# AMU_POC_final.net
KiCad netlist of a schematic drawn in Altium Designer
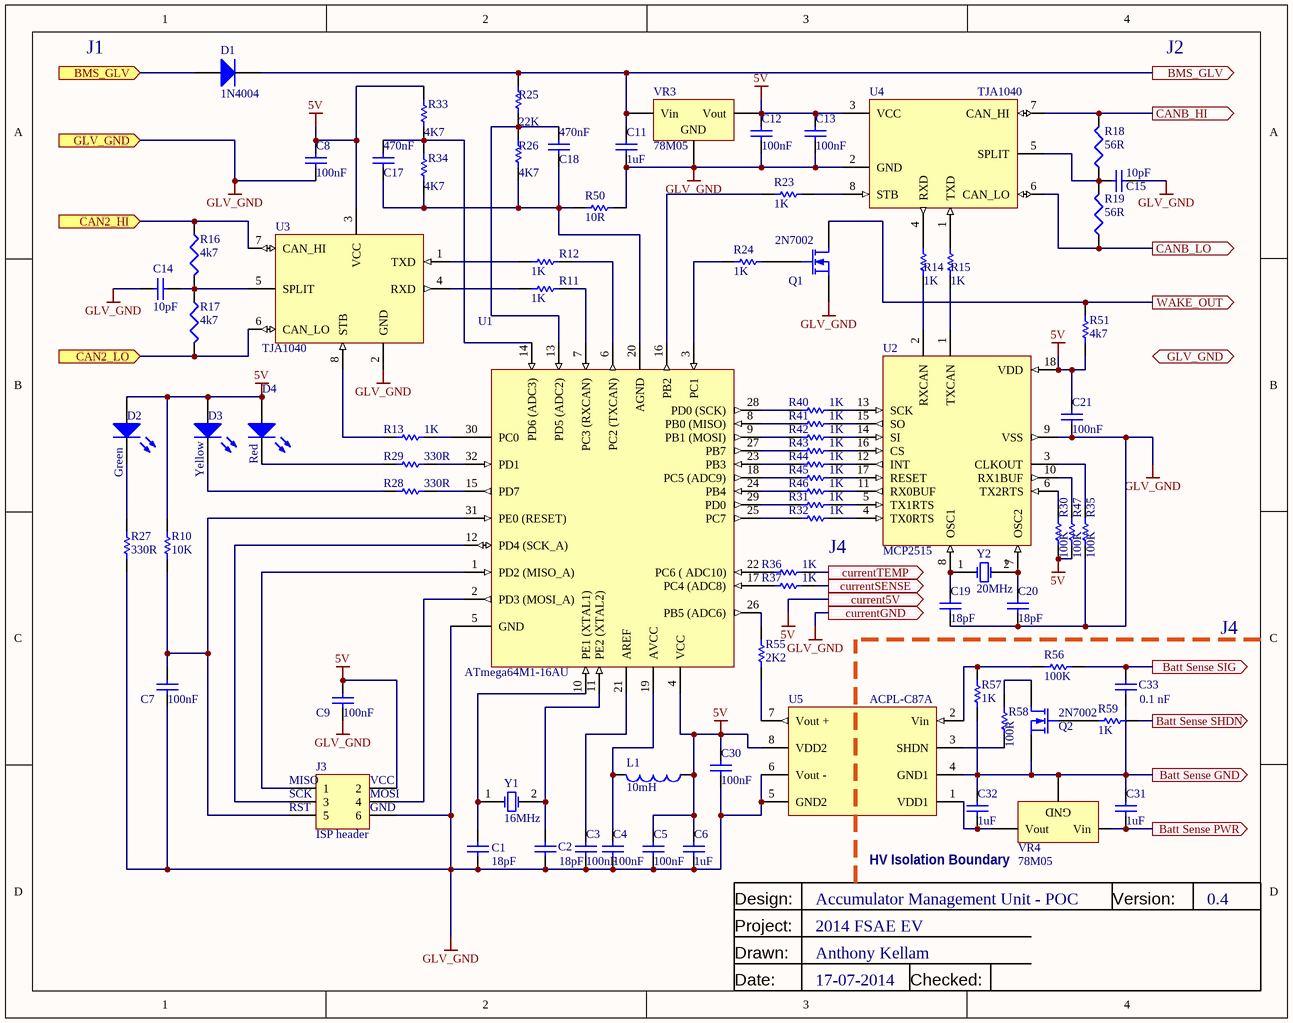
[diagram p0: AMU_POC_final.SchDoc]

(export (version "E")
  (design (tool "Eeschema 10.0.6"))
  (components
    (comp (ref "C1")
      (value "18pF")
      (footprint "0402")
      (description "Capacitor (Semiconductor SIM Model)")
      (fields (field (name "Comment") "Cap Semi") (field (name "PUBLISHER") "Altium Limited"))
      (libsource (lib "Miscellaneous Devices") (part "Cap Semi"))
    )
    (comp (ref "C2")
      (value "18pF")
      (footprint "0402")
      (description "Capacitor (Semiconductor SIM Model)")
      (fields (field (name "Comment") "Cap Semi") (field (name "PUBLISHER") "Altium Limited"))
      (libsource (lib "Miscellaneous Devices") (part "Cap Semi"))
    )
    (comp (ref "C3")
      (value "100nF")
      (footprint "0402")
      (description "Capacitor (Semiconductor SIM Model)")
      (fields (field (name "Comment") "Cap Semi") (field (name "PUBLISHER") "Altium Limited"))
      (libsource (lib "Miscellaneous Devices") (part "Cap Semi"))
    )
    (comp (ref "C4")
      (value "100nF")
      (footprint "0402")
      (description "Capacitor (Semiconductor SIM Model)")
      (fields (field (name "Comment") "Cap Semi") (field (name "PUBLISHER") "Altium Limited"))
      (libsource (lib "Miscellaneous Devices") (part "Cap Semi"))
    )
    (comp (ref "C5")
      (value "100nF")
      (footprint "0402")
      (description "Capacitor (Semiconductor SIM Model)")
      (fields (field (name "Comment") "Cap Semi") (field (name "PUBLISHER") "Altium Limited"))
      (libsource (lib "Miscellaneous Devices") (part "Cap Semi"))
    )
    (comp (ref "C6")
      (value "1uF")
      (footprint "0402")
      (description "Capacitor (Semiconductor SIM Model)")
      (fields (field (name "Comment") "Cap Semi") (field (name "PUBLISHER") "Altium Limited"))
      (libsource (lib "Miscellaneous Devices") (part "Cap Semi"))
    )
    (comp (ref "C7")
      (value "100nF")
      (footprint "0402")
      (description "Capacitor (Semiconductor SIM Model)")
      (fields (field (name "Comment") "Cap Semi") (field (name "PUBLISHER") "Altium Limited"))
      (libsource (lib "Miscellaneous Devices") (part "Cap Semi"))
    )
    (comp (ref "C8")
      (value "100nF")
      (footprint "0402")
      (description "Capacitor (Semiconductor SIM Model)")
      (fields (field (name "Comment") "Cap Semi") (field (name "PUBLISHER") "Altium Limited"))
      (libsource (lib "Miscellaneous Devices") (part "Cap Semi"))
    )
    (comp (ref "C9")
      (value "100nF")
      (footprint "0402")
      (description "Capacitor (Semiconductor SIM Model)")
      (fields (field (name "Comment") "Cap Semi") (field (name "PUBLISHER") "Altium Limited"))
      (libsource (lib "Miscellaneous Devices") (part "Cap Semi"))
    )
    (comp (ref "C11")
      (value "1uF")
      (footprint "0402")
      (description "Capacitor (Semiconductor SIM Model)")
      (fields (field (name "Comment") "Cap Semi") (field (name "PUBLISHER") "Altium Limited"))
      (libsource (lib "Miscellaneous Devices") (part "Cap Semi"))
    )
    (comp (ref "C12")
      (value "100nF")
      (footprint "0402")
      (description "Capacitor (Semiconductor SIM Model)")
      (fields (field (name "Comment") "Cap Semi") (field (name "PUBLISHER") "Altium Limited"))
      (libsource (lib "Miscellaneous Devices") (part "Cap Semi"))
    )
    (comp (ref "C13")
      (value "100nF")
      (footprint "0402")
      (description "Capacitor (Semiconductor SIM Model)")
      (fields (field (name "Comment") "Cap Semi") (field (name "PUBLISHER") "Altium Limited"))
      (libsource (lib "Miscellaneous Devices") (part "Cap Semi"))
    )
    (comp (ref "C14")
      (value "10pF")
      (footprint "0402")
      (description "Capacitor (Semiconductor SIM Model)")
      (fields (field (name "Comment") "Cap Semi") (field (name "PUBLISHER") "Altium Limited"))
      (libsource (lib "Miscellaneous Devices") (part "Cap Semi"))
    )
    (comp (ref "C15")
      (value "10pF")
      (footprint "0402")
      (description "Capacitor (Semiconductor SIM Model)")
      (fields (field (name "Comment") "Cap Semi") (field (name "PUBLISHER") "Altium Limited"))
      (libsource (lib "Miscellaneous Devices") (part "Cap Semi"))
    )
    (comp (ref "C17")
      (value "470nF")
      (footprint "0402")
      (description "Capacitor (Semiconductor SIM Model)")
      (fields (field (name "Comment") "Cap Semi") (field (name "PUBLISHER") "Altium Limited"))
      (libsource (lib "Miscellaneous Devices") (part "Cap Semi"))
    )
    (comp (ref "C18")
      (value "470nF")
      (footprint "0402")
      (description "Capacitor (Semiconductor SIM Model)")
      (fields (field (name "Comment") "Cap Semi") (field (name "PUBLISHER") "Altium Limited"))
      (libsource (lib "Miscellaneous Devices") (part "Cap Semi"))
    )
    (comp (ref "C19")
      (value "18pF")
      (footprint "0402")
      (description "Capacitor (Semiconductor SIM Model)")
      (fields (field (name "Comment") "Cap Semi") (field (name "PUBLISHER") "Altium Limited"))
      (libsource (lib "Miscellaneous Devices") (part "Cap Semi"))
    )
    (comp (ref "C20")
      (value "18pF")
      (footprint "0402")
      (description "Capacitor (Semiconductor SIM Model)")
      (fields (field (name "Comment") "Cap Semi") (field (name "PUBLISHER") "Altium Limited"))
      (libsource (lib "Miscellaneous Devices") (part "Cap Semi"))
    )
    (comp (ref "C21")
      (value "100nF")
      (footprint "0402")
      (description "Capacitor (Semiconductor SIM Model)")
      (fields (field (name "Comment") "Cap Semi") (field (name "PUBLISHER") "Altium Limited"))
      (libsource (lib "Miscellaneous Devices") (part "Cap Semi"))
    )
    (comp (ref "C30")
      (value "100nF")
      (footprint "0402")
      (description "Capacitor (Semiconductor SIM Model)")
      (fields (field (name "Comment") "Cap Semi") (field (name "PUBLISHER") "Altium Limited"))
      (libsource (lib "Miscellaneous Devices") (part "Cap Semi"))
    )
    (comp (ref "C31")
      (value "1uF")
      (footprint "0402")
      (description "Capacitor (Semiconductor SIM Model)")
      (fields (field (name "Comment") "Cap Semi") (field (name "PUBLISHER") "Altium Limited"))
      (libsource (lib "Miscellaneous Devices") (part "Cap Semi"))
    )
    (comp (ref "C32")
      (value "1uF")
      (footprint "0402")
      (description "Capacitor (Semiconductor SIM Model)")
      (fields (field (name "Comment") "Cap Semi") (field (name "PUBLISHER") "Altium Limited"))
      (libsource (lib "Miscellaneous Devices") (part "Cap Semi"))
    )
    (comp (ref "C33")
      (value "0.1 nF")
      (footprint "0402")
      (description "Capacitor (Semiconductor SIM Model)")
      (fields (field (name "Comment") "Cap Semi") (field (name "PUBLISHER") "Altium Limited"))
      (libsource (lib "Miscellaneous Devices") (part "Cap Semi"))
    )
    (comp (ref "D1")
      (value "1N4004")
      (footprint "SMC")
      (description "Default Diode")
      (fields (field (name "PUBLISHER") "Altium Limited"))
      (libsource (lib "Miscellaneous Devices") (part "Diode"))
    )
    (comp (ref "D2")
      (value "Green")
      (footprint "3.2X1.6X1.1")
      (description "Typical RED, GREEN, YELLOW, AMBER GaAs LED")
      (fields (field (name "PUBLISHER") "Altium Limited"))
      (libsource (lib "Miscellaneous Devices") (part "LED2"))
    )
    (comp (ref "D3")
      (value "Yellow")
      (footprint "3.2X1.6X1.1")
      (description "Typical RED, GREEN, YELLOW, AMBER GaAs LED")
      (fields (field (name "PUBLISHER") "Altium Limited"))
      (libsource (lib "Miscellaneous Devices") (part "LED2"))
    )
    (comp (ref "D4")
      (value "Red")
      (footprint "3.2X1.6X1.1")
      (description "Typical RED, GREEN, YELLOW, AMBER GaAs LED")
      (fields (field (name "PUBLISHER") "Altium Limited"))
      (libsource (lib "Miscellaneous Devices") (part "LED2"))
    )
    (comp (ref "J3")
      (value "ISP header")
      (footprint "HDR2X3")
      (description "Header, 3-Pin, Dual row")
      (fields (field (name "PUBLISHER") "Altium Limited"))
      (libsource (lib "Miscellaneous Connectors") (part "Header 3X2"))
    )
    (comp (ref "L1")
      (value "10mH")
      (footprint "0402-A")
      (description "Inductor")
      (fields (field (name "PUBLISHER") "Altium Limited"))
      (libsource (lib "Miscellaneous Devices") (part "Inductor"))
    )
    (comp (ref "Q1")
      (value "2N7002")
      (footprint "E3")
      (description "N-Channel MOSFET")
      (fields (field (name "PUBLISHER") "Altium Limited"))
      (libsource (lib "") (part "MOSFET-N_1"))
    )
    (comp (ref "Q2")
      (value "2N7002")
      (footprint "E3")
      (description "N-Channel MOSFET")
      (fields (field (name "PUBLISHER") "Altium Limited"))
      (libsource (lib "Miscellaneous Devices") (part "MOSFET-N"))
    )
    (comp (ref "R10")
      (value "10K")
      (footprint "AXIAL-0.3")
      (description "Resistor")
      (fields (field (name "Comment") "Res1") (field (name "PUBLISHER") "Altium Limited"))
      (libsource (lib "Miscellaneous Devices") (part "Res1"))
    )
    (comp (ref "R11")
      (value "1K")
      (footprint "AXIAL-0.3")
      (description "Resistor")
      (fields (field (name "Comment") "Res1") (field (name "PUBLISHER") "Altium Limited"))
      (libsource (lib "Miscellaneous Devices") (part "Res1"))
    )
    (comp (ref "R12")
      (value "1K")
      (footprint "AXIAL-0.3")
      (description "Resistor")
      (fields (field (name "Comment") "Res1") (field (name "PUBLISHER") "Altium Limited"))
      (libsource (lib "Miscellaneous Devices") (part "Res1"))
    )
    (comp (ref "R13")
      (value "1K")
      (footprint "AXIAL-0.3")
      (description "Resistor")
      (fields (field (name "Comment") "Res1") (field (name "PUBLISHER") "Altium Limited"))
      (libsource (lib "Miscellaneous Devices") (part "Res1"))
    )
    (comp (ref "R14")
      (value "1K")
      (footprint "AXIAL-0.3")
      (description "Resistor")
      (fields (field (name "Comment") "Res1") (field (name "PUBLISHER") "Altium Limited"))
      (libsource (lib "Miscellaneous Devices") (part "Res1"))
    )
    (comp (ref "R15")
      (value "1K")
      (footprint "AXIAL-0.3")
      (description "Resistor")
      (fields (field (name "Comment") "Res1") (field (name "PUBLISHER") "Altium Limited"))
      (libsource (lib "Miscellaneous Devices") (part "Res1"))
    )
    (comp (ref "R16")
      (value "4k7")
      (footprint "J1-0603")
      (description "Resistor")
      (fields (field (name "Comment") "Res3") (field (name "PUBLISHER") "Altium Limited"))
      (libsource (lib "Miscellaneous Devices") (part "Res3"))
    )
    (comp (ref "R17")
      (value "4k7")
      (footprint "J1-0603")
      (description "Resistor")
      (fields (field (name "Comment") "Res3") (field (name "PUBLISHER") "Altium Limited"))
      (libsource (lib "Miscellaneous Devices") (part "Res3"))
    )
    (comp (ref "R18")
      (value "56R")
      (footprint "J1-0603")
      (description "Resistor")
      (fields (field (name "Comment") "Res3") (field (name "PUBLISHER") "Altium Limited"))
      (libsource (lib "Miscellaneous Devices") (part "Res3"))
    )
    (comp (ref "R19")
      (value "56R")
      (footprint "J1-0603")
      (description "Resistor")
      (fields (field (name "Comment") "Res3") (field (name "PUBLISHER") "Altium Limited"))
      (libsource (lib "Miscellaneous Devices") (part "Res3"))
    )
    (comp (ref "R23")
      (value "1K")
      (footprint "AXIAL-0.3")
      (description "Resistor")
      (fields (field (name "Comment") "Res1") (field (name "PUBLISHER") "Altium Limited"))
      (libsource (lib "Miscellaneous Devices") (part "Res1"))
    )
    (comp (ref "R24")
      (value "1K")
      (footprint "AXIAL-0.3")
      (description "Resistor")
      (fields (field (name "Comment") "Res1") (field (name "PUBLISHER") "Altium Limited"))
      (libsource (lib "Miscellaneous Devices") (part "Res1"))
    )
    (comp (ref "R25")
      (value "22K")
      (footprint "AXIAL-0.3")
      (description "Resistor")
      (fields (field (name "Comment") "Res1") (field (name "PUBLISHER") "Altium Limited"))
      (libsource (lib "Miscellaneous Devices") (part "Res1"))
    )
    (comp (ref "R26")
      (value "4K7")
      (footprint "AXIAL-0.3")
      (description "Resistor")
      (fields (field (name "Comment") "Res1") (field (name "PUBLISHER") "Altium Limited"))
      (libsource (lib "Miscellaneous Devices") (part "Res1"))
    )
    (comp (ref "R27")
      (value "330R")
      (footprint "AXIAL-0.3")
      (description "Resistor")
      (fields (field (name "Comment") "Res1") (field (name "PUBLISHER") "Altium Limited"))
      (libsource (lib "Miscellaneous Devices") (part "Res1"))
    )
    (comp (ref "R28")
      (value "330R")
      (footprint "AXIAL-0.3")
      (description "Resistor")
      (fields (field (name "Comment") "Res1") (field (name "PUBLISHER") "Altium Limited"))
      (libsource (lib "Miscellaneous Devices") (part "Res1"))
    )
    (comp (ref "R29")
      (value "330R")
      (footprint "AXIAL-0.3")
      (description "Resistor")
      (fields (field (name "Comment") "Res1") (field (name "PUBLISHER") "Altium Limited"))
      (libsource (lib "Miscellaneous Devices") (part "Res1"))
    )
    (comp (ref "R30")
      (value "100K")
      (footprint "AXIAL-0.3")
      (description "Resistor")
      (fields (field (name "Comment") "Res1") (field (name "PUBLISHER") "Altium Limited"))
      (libsource (lib "Miscellaneous Devices") (part "Res1"))
    )
    (comp (ref "R31")
      (value "1K")
      (footprint "AXIAL-0.3")
      (description "Resistor")
      (fields (field (name "Comment") "Res1") (field (name "PUBLISHER") "Altium Limited"))
      (libsource (lib "Miscellaneous Devices") (part "Res1"))
    )
    (comp (ref "R32")
      (value "1K")
      (footprint "AXIAL-0.3")
      (description "Resistor")
      (fields (field (name "Comment") "Res1") (field (name "PUBLISHER") "Altium Limited"))
      (libsource (lib "Miscellaneous Devices") (part "Res1"))
    )
    (comp (ref "R33")
      (value "4K7")
      (footprint "AXIAL-0.3")
      (description "Resistor")
      (fields (field (name "Comment") "Res1") (field (name "PUBLISHER") "Altium Limited"))
      (libsource (lib "Miscellaneous Devices") (part "Res1"))
    )
    (comp (ref "R34")
      (value "4K7")
      (footprint "AXIAL-0.3")
      (description "Resistor")
      (fields (field (name "Comment") "Res1") (field (name "PUBLISHER") "Altium Limited"))
      (libsource (lib "Miscellaneous Devices") (part "Res1"))
    )
    (comp (ref "R35")
      (value "100K")
      (footprint "AXIAL-0.3")
      (description "Resistor")
      (fields (field (name "Comment") "Res1") (field (name "PUBLISHER") "Altium Limited"))
      (libsource (lib "Miscellaneous Devices") (part "Res1"))
    )
    (comp (ref "R36")
      (value "1K")
      (footprint "AXIAL-0.3")
      (description "Resistor")
      (fields (field (name "Comment") "Res1") (field (name "PUBLISHER") "Altium Limited"))
      (libsource (lib "Miscellaneous Devices") (part "Res1"))
    )
    (comp (ref "R37")
      (value "1K")
      (footprint "AXIAL-0.3")
      (description "Resistor")
      (fields (field (name "Comment") "Res1") (field (name "PUBLISHER") "Altium Limited"))
      (libsource (lib "Miscellaneous Devices") (part "Res1"))
    )
    (comp (ref "R40")
      (value "1K")
      (footprint "AXIAL-0.3")
      (description "Resistor")
      (fields (field (name "Comment") "Res1") (field (name "PUBLISHER") "Altium Limited"))
      (libsource (lib "Miscellaneous Devices") (part "Res1"))
    )
    (comp (ref "R41")
      (value "1K")
      (footprint "AXIAL-0.3")
      (description "Resistor")
      (fields (field (name "Comment") "Res1") (field (name "PUBLISHER") "Altium Limited"))
      (libsource (lib "Miscellaneous Devices") (part "Res1"))
    )
    (comp (ref "R42")
      (value "1K")
      (footprint "AXIAL-0.3")
      (description "Resistor")
      (fields (field (name "Comment") "Res1") (field (name "PUBLISHER") "Altium Limited"))
      (libsource (lib "Miscellaneous Devices") (part "Res1"))
    )
    (comp (ref "R43")
      (value "1K")
      (footprint "AXIAL-0.3")
      (description "Resistor")
      (fields (field (name "Comment") "Res1") (field (name "PUBLISHER") "Altium Limited"))
      (libsource (lib "Miscellaneous Devices") (part "Res1"))
    )
    (comp (ref "R44")
      (value "1K")
      (footprint "AXIAL-0.3")
      (description "Resistor")
      (fields (field (name "Comment") "Res1") (field (name "PUBLISHER") "Altium Limited"))
      (libsource (lib "Miscellaneous Devices") (part "Res1"))
    )
    (comp (ref "R45")
      (value "1K")
      (footprint "AXIAL-0.3")
      (description "Resistor")
      (fields (field (name "Comment") "Res1") (field (name "PUBLISHER") "Altium Limited"))
      (libsource (lib "Miscellaneous Devices") (part "Res1"))
    )
    (comp (ref "R46")
      (value "1K")
      (footprint "AXIAL-0.3")
      (description "Resistor")
      (fields (field (name "Comment") "Res1") (field (name "PUBLISHER") "Altium Limited"))
      (libsource (lib "Miscellaneous Devices") (part "Res1"))
    )
    (comp (ref "R47")
      (value "100K")
      (footprint "AXIAL-0.3")
      (description "Resistor")
      (fields (field (name "Comment") "Res1") (field (name "PUBLISHER") "Altium Limited"))
      (libsource (lib "Miscellaneous Devices") (part "Res1"))
    )
    (comp (ref "R50")
      (value "10R")
      (footprint "AXIAL-0.3")
      (description "Resistor")
      (fields (field (name "Comment") "Res1") (field (name "PUBLISHER") "Altium Limited"))
      (libsource (lib "Miscellaneous Devices") (part "Res1"))
    )
    (comp (ref "R51")
      (value "4k7")
      (footprint "AXIAL-0.3")
      (description "Resistor")
      (fields (field (name "Comment") "Res1") (field (name "PUBLISHER") "Altium Limited"))
      (libsource (lib "Miscellaneous Devices") (part "Res1"))
    )
    (comp (ref "R55")
      (value "2K2")
      (footprint "AXIAL-0.3")
      (description "Resistor")
      (fields (field (name "Comment") "Res1") (field (name "PUBLISHER") "Altium Limited"))
      (libsource (lib "Miscellaneous Devices") (part "Res1"))
    )
    (comp (ref "R56")
      (value "100K")
      (footprint "AXIAL-0.3")
      (description "Resistor")
      (fields (field (name "Comment") "Res1") (field (name "PUBLISHER") "Altium Limited"))
      (libsource (lib "Miscellaneous Devices") (part "Res1"))
    )
    (comp (ref "R57")
      (value "1K")
      (footprint "AXIAL-0.3")
      (description "Resistor")
      (fields (field (name "Comment") "Res1") (field (name "PUBLISHER") "Altium Limited"))
      (libsource (lib "Miscellaneous Devices") (part "Res1"))
    )
    (comp (ref "R58")
      (value "100R")
      (footprint "AXIAL-0.3")
      (description "Resistor")
      (fields (field (name "Comment") "Res1") (field (name "PUBLISHER") "Altium Limited"))
      (libsource (lib "Miscellaneous Devices") (part "Res1"))
    )
    (comp (ref "R59")
      (value "1K")
      (footprint "AXIAL-0.3")
      (description "Resistor")
      (fields (field (name "Comment") "Res1") (field (name "PUBLISHER") "Altium Limited"))
      (libsource (lib "Miscellaneous Devices") (part "Res1"))
    )
    (comp (ref "U1")
      (value "ATmega64M1-16AU")
      (footprint "32A_L")
      (description "8-Bit AVR Microcontroller with 8K Bytes of In-System Programmable Flash Memory")
      (fields (field (name "PUBLISHER") "Altium Limited"))
      (libsource (lib "Atmel Microcontroller 8-Bit AVR") (part "ATmega8-16AC"))
    )
    (comp (ref "U2")
      (value "MCP2515")
      (footprint "Q-18")
      (description "Low-Noise, Precision Instrumentation Amplifier")
      (fields (field (name "PUBLISHER") "Altium Limited"))
      (libsource (lib "AD Instrumentation Amplifier") (part "AMP01AX/883"))
    )
    (comp (ref "U3")
      (value "TJA1040")
      (footprint "8S2_L")
      (description "Isolated CAN transceiver")
      (fields (field (name "PUBLISHER") "Altium Limited"))
      (libsource (lib "") (part "AT90S2343-10SI_1"))
    )
    (comp (ref "U4")
      (value "TJA1040")
      (footprint "8S2_L")
      (description "Isolated CAN transceiver")
      (fields (field (name "PUBLISHER") "Altium Limited"))
      (libsource (lib "") (part "AT90S2343-10SI_2"))
    )
    (comp (ref "U5")
      (value "ACPL-C87A")
      (footprint "8S2_L")
      (description "Isolated CAN transceiver")
      (fields (field (name "PUBLISHER") "Altium Limited"))
      (libsource (lib "Atmel Microcontroller 8-Bit AVR") (part "AT90S2343-10SI"))
    )
    (comp (ref "VR3")
      (value "78M05")
      (footprint "D2PAK")
      (fields (field (name "PUBLISHER") "Altium Limited"))
      (libsource (lib "") (part "Volt Reg_1"))
    )
    (comp (ref "VR4")
      (value "78M05")
      (footprint "D2PAK")
      (fields (field (name "PUBLISHER") "Altium Limited"))
      (libsource (lib "Miscellaneous Devices") (part "Volt Reg"))
    )
    (comp (ref "Y1")
      (value "16MHz")
      (footprint "R38")
      (description "Crystal Oscillator")
      (fields (field (name "PUBLISHER") "Altium Limited"))
      (libsource (lib "Miscellaneous Devices") (part "XTAL"))
    )
    (comp (ref "Y2")
      (value "20MHz")
      (footprint "R38")
      (description "Crystal Oscillator")
      (fields (field (name "PUBLISHER") "Altium Limited"))
      (libsource (lib "Miscellaneous Devices") (part "XTAL"))
    )
  )
  (nets
    (net (code "1") (name "/BMS_GLV") (class "Default")
      (node (ref "C11") (pin "2") (pinfunction "2_2") (pintype "passive"))
      (node (ref "D1") (pin "1") (pinfunction "A_1") (pintype "passive"))
      (node (ref "D1") (pin "2") (pinfunction "K_2") (pintype "passive"))
      (node (ref "R25") (pin "1") (pinfunction "1_1") (pintype "passive"))
      (node (ref "VR3") (pin "1") (pinfunction "Vin_1") (pintype "passive"))
    )
    (net (code "2") (name "/Batt Sense GND") (class "Default")
      (node (ref "C31") (pin "2") (pinfunction "2_2") (pintype "passive"))
      (node (ref "C32") (pin "2") (pinfunction "2_2") (pintype "passive"))
      (node (ref "C33") (pin "1") (pinfunction "1_1") (pintype "passive"))
      (node (ref "Q2") (pin "3") (pinfunction "S_3") (pintype "passive"))
      (node (ref "R57") (pin "1") (pinfunction "1_1") (pintype "passive"))
      (node (ref "U5") (pin "4") (pinfunction "GND1_4") (pintype "power_in"))
      (node (ref "VR4") (pin "2") (pinfunction "GND_2") (pintype "passive"))
    )
    (net (code "3") (name "/Batt Sense PWR") (class "Default")
      (node (ref "C31") (pin "1") (pinfunction "1_1") (pintype "passive"))
      (node (ref "VR4") (pin "1") (pinfunction "Vin_1") (pintype "passive"))
    )
    (net (code "4") (name "/Batt Sense SHDN") (class "Default")
      (node (ref "R59") (pin "1") (pinfunction "1_1") (pintype "passive"))
    )
    (net (code "5") (name "/Batt Sense SIG") (class "Default")
      (node (ref "C33") (pin "2") (pinfunction "2_2") (pintype "passive"))
      (node (ref "R56") (pin "1") (pinfunction "1_1") (pintype "passive"))
    )
    (net (code "6") (name "/CAN2_HI") (class "Default")
      (node (ref "R16") (pin "1") (pinfunction "1_1") (pintype "passive"))
      (node (ref "U3") (pin "7") (pinfunction "CAN_HI_7") (pintype "bidirectional"))
    )
    (net (code "7") (name "/CAN2_LO") (class "Default")
      (node (ref "R17") (pin "2") (pinfunction "2_2") (pintype "passive"))
      (node (ref "U3") (pin "6") (pinfunction "CAN_LO_6") (pintype "bidirectional"))
    )
    (net (code "8") (name "/CANB_HI") (class "Default")
      (node (ref "R18") (pin "2") (pinfunction "2_2") (pintype "passive"))
      (node (ref "U4") (pin "7") (pinfunction "CAN_HI_7") (pintype "bidirectional"))
    )
    (net (code "9") (name "/CANB_LO") (class "Default")
      (node (ref "R19") (pin "1") (pinfunction "1_1") (pintype "passive"))
      (node (ref "U4") (pin "6") (pinfunction "CAN_LO_6") (pintype "bidirectional"))
    )
    (net (code "10") (name "/WAKE_OUT") (class "Default")
      (node (ref "Q1") (pin "1") (pinfunction "D_1") (pintype "passive"))
      (node (ref "R51") (pin "2") (pinfunction "2_2") (pintype "passive"))
    )
    (net (code "11") (name "/currentSENSE") (class "Default")
      (node (ref "R37") (pin "2") (pinfunction "2_2") (pintype "passive"))
    )
    (net (code "12") (name "/currentTEMP") (class "Default")
      (node (ref "R36") (pin "2") (pinfunction "2_2") (pintype "passive"))
    )
    (net (code "13") (name "5V") (class "Default")
      (node (ref "C12") (pin "2") (pinfunction "2_2") (pintype "passive"))
      (node (ref "C13") (pin "2") (pinfunction "2_2") (pintype "passive"))
      (node (ref "C21") (pin "2") (pinfunction "2_2") (pintype "passive"))
      (node (ref "C30") (pin "1") (pinfunction "1_1") (pintype "passive"))
      (node (ref "C5") (pin "1") (pinfunction "1_1") (pintype "passive"))
      (node (ref "C6") (pin "1") (pinfunction "1_1") (pintype "passive"))
      (node (ref "C8") (pin "2") (pinfunction "2_2") (pintype "passive"))
      (node (ref "C9") (pin "2") (pinfunction "2_2") (pintype "passive"))
      (node (ref "D2") (pin "1") (pinfunction "A_1") (pintype "passive"))
      (node (ref "D3") (pin "1") (pinfunction "A_1") (pintype "passive"))
      (node (ref "D4") (pin "1") (pinfunction "A_1") (pintype "passive"))
      (node (ref "J3") (pin "2") (pinfunction "2_2") (pintype "passive"))
      (node (ref "L1") (pin "1") (pinfunction "1_1") (pintype "passive"))
      (node (ref "R10") (pin "2") (pinfunction "2_2") (pintype "passive"))
      (node (ref "R30") (pin "2") (pinfunction "2_2") (pintype "passive"))
      (node (ref "R33") (pin "1") (pinfunction "1_1") (pintype "passive"))
      (node (ref "R47") (pin "2") (pinfunction "2_2") (pintype "passive"))
      (node (ref "R51") (pin "1") (pinfunction "1_1") (pintype "passive"))
      (node (ref "U1") (pin "4") (pinfunction "VCC_4") (pintype "power_in"))
      (node (ref "U2") (pin "18") (pinfunction "VDD_18") (pintype "input"))
      (node (ref "U3") (pin "3") (pinfunction "VCC_3") (pintype "power_in"))
      (node (ref "U4") (pin "3") (pinfunction "VCC_3") (pintype "power_in"))
      (node (ref "U5") (pin "8") (pinfunction "VDD2_8") (pintype "power_in"))
      (node (ref "VR3") (pin "3") (pinfunction "Vout_3") (pintype "passive"))
    )
    (net (code "14") (name "GLV_GND") (class "Default")
      (node (ref "C1") (pin "1") (pinfunction "1_1") (pintype "passive"))
      (node (ref "C11") (pin "1") (pinfunction "1_1") (pintype "passive"))
      (node (ref "C12") (pin "1") (pinfunction "1_1") (pintype "passive"))
      (node (ref "C13") (pin "1") (pinfunction "1_1") (pintype "passive"))
      (node (ref "C14") (pin "1") (pinfunction "1_1") (pintype "passive"))
      (node (ref "C15") (pin "1") (pinfunction "1_1") (pintype "passive"))
      (node (ref "C19") (pin "1") (pinfunction "1_1") (pintype "passive"))
      (node (ref "C2") (pin "1") (pinfunction "1_1") (pintype "passive"))
      (node (ref "C20") (pin "1") (pinfunction "1_1") (pintype "passive"))
      (node (ref "C21") (pin "1") (pinfunction "1_1") (pintype "passive"))
      (node (ref "C3") (pin "2") (pinfunction "2_2") (pintype "passive"))
      (node (ref "C30") (pin "2") (pinfunction "2_2") (pintype "passive"))
      (node (ref "C4") (pin "2") (pinfunction "2_2") (pintype "passive"))
      (node (ref "C5") (pin "2") (pinfunction "2_2") (pintype "passive"))
      (node (ref "C6") (pin "2") (pinfunction "2_2") (pintype "passive"))
      (node (ref "C7") (pin "1") (pinfunction "1_1") (pintype "passive"))
      (node (ref "C8") (pin "1") (pinfunction "1_1") (pintype "passive"))
      (node (ref "C9") (pin "1") (pinfunction "1_1") (pintype "passive"))
      (node (ref "J3") (pin "6") (pinfunction "6_6") (pintype "passive"))
      (node (ref "Q1") (pin "3") (pinfunction "S_3") (pintype "passive"))
      (node (ref "R27") (pin "1") (pinfunction "1_1") (pintype "passive"))
      (node (ref "R35") (pin "2") (pinfunction "2_2") (pintype "passive"))
      (node (ref "R50") (pin "2") (pinfunction "2_2") (pintype "passive"))
      (node (ref "U1") (pin "5") (pinfunction "GND_5") (pintype "power_in"))
      (node (ref "U2") (pin "9") (pinfunction "VSS_9") (pintype "output"))
      (node (ref "U3") (pin "2") (pinfunction "GND_2") (pintype "power_in"))
      (node (ref "U4") (pin "2") (pinfunction "GND_2") (pintype "power_in"))
      (node (ref "U5") (pin "5") (pinfunction "GND2_5") (pintype "power_in"))
      (node (ref "U5") (pin "6") (pinfunction "Vout_-_6") (pintype "power_in"))
      (node (ref "VR3") (pin "2") (pinfunction "GND_2") (pintype "passive"))
    )
    (net (code "15") (name "Net-(D2-K)") (class "Default")
      (node (ref "D2") (pin "2") (pinfunction "K_2") (pintype "passive"))
      (node (ref "R27") (pin "2") (pinfunction "2_2") (pintype "passive"))
    )
    (net (code "16") (name "Net-(D3-K)") (class "Default")
      (node (ref "D3") (pin "2") (pinfunction "K_2") (pintype "passive"))
      (node (ref "R28") (pin "1") (pinfunction "1_1") (pintype "passive"))
    )
    (net (code "17") (name "Net-(D4-K)") (class "Default")
      (node (ref "D4") (pin "2") (pinfunction "K_2") (pintype "passive"))
      (node (ref "R29") (pin "1") (pinfunction "1_1") (pintype "passive"))
    )
    (net (code "18") (name "Net-(Q1-G)") (class "Default")
      (node (ref "Q1") (pin "2") (pinfunction "G_2") (pintype "passive"))
      (node (ref "R24") (pin "2") (pinfunction "2_2") (pintype "passive"))
    )
    (net (code "19") (name "Net-(Q2-D)") (class "Default")
      (node (ref "Q2") (pin "1") (pinfunction "D_1") (pintype "passive"))
      (node (ref "R58") (pin "2") (pinfunction "2_2") (pintype "passive"))
    )
    (net (code "20") (name "Net-(Q2-G)") (class "Default")
      (node (ref "Q2") (pin "2") (pinfunction "G_2") (pintype "passive"))
      (node (ref "R59") (pin "2") (pinfunction "2_2") (pintype "passive"))
    )
    (net (code "21") (name "Net-(U1-AGND)") (class "Default")
      (node (ref "C17") (pin "1") (pinfunction "1_1") (pintype "passive"))
      (node (ref "C18") (pin "1") (pinfunction "1_1") (pintype "passive"))
      (node (ref "R26") (pin "2") (pinfunction "2_2") (pintype "passive"))
      (node (ref "R34") (pin "2") (pinfunction "2_2") (pintype "passive"))
      (node (ref "R50") (pin "1") (pinfunction "1_1") (pintype "passive"))
      (node (ref "U1") (pin "20") (pinfunction "AGND_20") (pintype "power_in"))
    )
    (net (code "22") (name "Net-(U1-AREF)") (class "Default")
      (node (ref "C3") (pin "1") (pinfunction "1_1") (pintype "passive"))
      (node (ref "U1") (pin "21") (pinfunction "AREF_21") (pintype "power_in"))
    )
    (net (code "23") (name "Net-(U1-AVCC)") (class "Default")
      (node (ref "C4") (pin "1") (pinfunction "1_1") (pintype "passive"))
      (node (ref "L1") (pin "2") (pinfunction "2_2") (pintype "passive"))
      (node (ref "U1") (pin "19") (pinfunction "AVCC_19") (pintype "power_in"))
    )
    (net (code "24") (name "Net-(U1-PB0_(MISO))") (class "Default")
      (node (ref "R41") (pin "1") (pinfunction "1_1") (pintype "passive"))
      (node (ref "U1") (pin "8") (pinfunction "PB0_(MISO)_8") (pintype "input"))
    )
    (net (code "25") (name "Net-(U1-PB1_(MOSI))") (class "Default")
      (node (ref "R42") (pin "1") (pinfunction "1_1") (pintype "passive"))
      (node (ref "U1") (pin "9") (pinfunction "PB1_(MOSI)_9") (pintype "output"))
    )
    (net (code "26") (name "Net-(U1-PB2)") (class "Default")
      (node (ref "R23") (pin "1") (pinfunction "1_1") (pintype "passive"))
      (node (ref "U1") (pin "16") (pinfunction "PB2_16") (pintype "output"))
    )
    (net (code "27") (name "Net-(U1-PB3)") (class "Default")
      (node (ref "R44") (pin "1") (pinfunction "1_1") (pintype "passive"))
      (node (ref "U1") (pin "23") (pinfunction "PB3_23") (pintype "input"))
    )
    (net (code "28") (name "Net-(U1-PB4)") (class "Default")
      (node (ref "R46") (pin "1") (pinfunction "1_1") (pintype "passive"))
      (node (ref "U1") (pin "24") (pinfunction "PB4_24") (pintype "input"))
    )
    (net (code "29") (name "Net-(U1-PB5_(ADC6))") (class "Default")
      (node (ref "R55") (pin "2") (pinfunction "2_2") (pintype "passive"))
      (node (ref "U1") (pin "26") (pinfunction "PB5_(ADC6)_26") (pintype "output"))
    )
    (net (code "30") (name "Net-(U1-PB7)") (class "Default")
      (node (ref "R43") (pin "1") (pinfunction "1_1") (pintype "passive"))
      (node (ref "U1") (pin "27") (pinfunction "PB7_27") (pintype "output"))
    )
    (net (code "31") (name "Net-(U1-PC0)") (class "Default")
      (node (ref "R13") (pin "2") (pinfunction "2_2") (pintype "passive"))
      (node (ref "U1") (pin "30") (pinfunction "PC0_30") (pintype "passive"))
    )
    (net (code "32") (name "Net-(U1-PC1)") (class "Default")
      (node (ref "R24") (pin "1") (pinfunction "1_1") (pintype "passive"))
      (node (ref "U1") (pin "3") (pinfunction "PC1_3") (pintype "input"))
    )
    (net (code "33") (name "Net-(U1-PC2_(TXCAN))") (class "Default")
      (node (ref "R12") (pin "1") (pinfunction "1_1") (pintype "passive"))
      (node (ref "U1") (pin "6") (pinfunction "PC2_(TXCAN)_6") (pintype "output"))
    )
    (net (code "34") (name "Net-(U1-PC3_(RXCAN))") (class "Default")
      (node (ref "R11") (pin "2") (pinfunction "2_2") (pintype "passive"))
      (node (ref "U1") (pin "7") (pinfunction "PC3_(RXCAN)_7") (pintype "input"))
    )
    (net (code "35") (name "Net-(U1-PC4_(ADC8))") (class "Default")
      (node (ref "R37") (pin "1") (pinfunction "1_1") (pintype "passive"))
      (node (ref "U1") (pin "17") (pinfunction "PC4_(ADC8)_17") (pintype "input"))
    )
    (net (code "36") (name "Net-(U1-PC5_(ADC9))") (class "Default")
      (node (ref "R45") (pin "1") (pinfunction "1_1") (pintype "passive"))
      (node (ref "U1") (pin "18") (pinfunction "PC5_(ADC9)_18") (pintype "output"))
    )
    (net (code "37") (name "Net-(U1-PC6_(_ADC10))") (class "Default")
      (node (ref "R36") (pin "1") (pinfunction "1_1") (pintype "passive"))
      (node (ref "U1") (pin "22") (pinfunction "PC6_(_ADC10)_22") (pintype "input"))
    )
    (net (code "38") (name "Net-(U1-PC7)") (class "Default")
      (node (ref "R32") (pin "1") (pinfunction "1_1") (pintype "passive"))
      (node (ref "U1") (pin "25") (pinfunction "PC7_25") (pintype "output"))
    )
    (net (code "39") (name "Net-(U1-PD0)") (class "Default")
      (node (ref "R31") (pin "1") (pinfunction "1_1") (pintype "passive"))
      (node (ref "U1") (pin "29") (pinfunction "PD0_29") (pintype "output"))
    )
    (net (code "40") (name "Net-(U1-PD0_(SCK))") (class "Default")
      (node (ref "R40") (pin "1") (pinfunction "1_1") (pintype "passive"))
      (node (ref "U1") (pin "28") (pinfunction "PD0_(SCK)_28") (pintype "output"))
    )
    (net (code "41") (name "Net-(U1-PD1)") (class "Default")
      (node (ref "R29") (pin "2") (pinfunction "2_2") (pintype "passive"))
      (node (ref "U1") (pin "32") (pinfunction "PD1_32") (pintype "input"))
    )
    (net (code "42") (name "Net-(U1-PD2_(MISO_A))") (class "Default")
      (node (ref "J3") (pin "1") (pinfunction "1_1") (pintype "passive"))
      (node (ref "U1") (pin "1") (pinfunction "PD2_(MISO_A)_1") (pintype "input"))
    )
    (net (code "43") (name "Net-(U1-PD3_(MOSI_A))") (class "Default")
      (node (ref "J3") (pin "4") (pinfunction "4_4") (pintype "passive"))
      (node (ref "U1") (pin "2") (pinfunction "PD3_(MOSI_A)_2") (pintype "output"))
    )
    (net (code "44") (name "Net-(U1-PD4_(SCK_A))") (class "Default")
      (node (ref "J3") (pin "3") (pinfunction "3_3") (pintype "passive"))
      (node (ref "U1") (pin "12") (pinfunction "PD4_(SCK_A)_12") (pintype "bidirectional"))
    )
    (net (code "45") (name "Net-(U1-PD5_(ADC2))") (class "Default")
      (node (ref "C18") (pin "2") (pinfunction "2_2") (pintype "passive"))
      (node (ref "R25") (pin "2") (pinfunction "2_2") (pintype "passive"))
      (node (ref "R26") (pin "1") (pinfunction "1_1") (pintype "passive"))
      (node (ref "U1") (pin "13") (pinfunction "PD5_(ADC2)_13") (pintype "input"))
    )
    (net (code "46") (name "Net-(U1-PD6_(ADC3))") (class "Default")
      (node (ref "C17") (pin "2") (pinfunction "2_2") (pintype "passive"))
      (node (ref "R33") (pin "2") (pinfunction "2_2") (pintype "passive"))
      (node (ref "R34") (pin "1") (pinfunction "1_1") (pintype "passive"))
      (node (ref "U1") (pin "14") (pinfunction "PD6_(ADC3)_14") (pintype "input"))
    )
    (net (code "47") (name "Net-(U1-PD7)") (class "Default")
      (node (ref "R28") (pin "2") (pinfunction "2_2") (pintype "passive"))
      (node (ref "U1") (pin "15") (pinfunction "PD7_15") (pintype "output"))
    )
    (net (code "48") (name "Net-(U1-PE0_(RESET))") (class "Default")
      (node (ref "C7") (pin "2") (pinfunction "2_2") (pintype "passive"))
      (node (ref "J3") (pin "5") (pinfunction "5_5") (pintype "passive"))
      (node (ref "R10") (pin "1") (pinfunction "1_1") (pintype "passive"))
      (node (ref "U1") (pin "31") (pinfunction "PE0_(RESET)_31") (pintype "input"))
    )
    (net (code "49") (name "Net-(U1-PE1_(XTAL1))") (class "Default")
      (node (ref "C1") (pin "2") (pinfunction "2_2") (pintype "passive"))
      (node (ref "U1") (pin "10") (pinfunction "PE1_(XTAL1)_10") (pintype "input"))
      (node (ref "Y1") (pin "1") (pinfunction "OSC1_1") (pintype "passive"))
    )
    (net (code "50") (name "Net-(U1-PE2_(XTAL2))") (class "Default")
      (node (ref "C2") (pin "2") (pinfunction "2_2") (pintype "passive"))
      (node (ref "U1") (pin "11") (pinfunction "PE2_(XTAL2)_11") (pintype "input"))
      (node (ref "Y1") (pin "2") (pinfunction "OSC2_2") (pintype "passive"))
    )
    (net (code "51") (name "Net-(U2-CLKOUT)") (class "Default")
      (node (ref "R35") (pin "1") (pinfunction "1_1") (pintype "passive"))
      (node (ref "U2") (pin "3") (pinfunction "CLKOUT_3") (pintype "passive"))
    )
    (net (code "52") (name "Net-(U2-CS)") (class "Default")
      (node (ref "R43") (pin "2") (pinfunction "2_2") (pintype "passive"))
      (node (ref "U2") (pin "16") (pinfunction "CS_16") (pintype "input"))
    )
    (net (code "53") (name "Net-(U2-INT)") (class "Default")
      (node (ref "R44") (pin "2") (pinfunction "2_2") (pintype "passive"))
      (node (ref "U2") (pin "12") (pinfunction "INT_12") (pintype "output"))
    )
    (net (code "54") (name "Net-(U2-OSC1)") (class "Default")
      (node (ref "C19") (pin "2") (pinfunction "2_2") (pintype "passive"))
      (node (ref "U2") (pin "8") (pinfunction "OSC1_8") (pintype "input"))
      (node (ref "Y2") (pin "1") (pinfunction "OSC1_1") (pintype "passive"))
    )
    (net (code "55") (name "Net-(U2-OSC2)") (class "Default")
      (node (ref "C20") (pin "2") (pinfunction "2_2") (pintype "passive"))
      (node (ref "U2") (pin "7") (pinfunction "OSC2_7") (pintype "input"))
      (node (ref "Y2") (pin "2") (pinfunction "OSC2_2") (pintype "passive"))
    )
    (net (code "56") (name "Net-(U2-RESET)") (class "Default")
      (node (ref "R45") (pin "2") (pinfunction "2_2") (pintype "passive"))
      (node (ref "U2") (pin "17") (pinfunction "RESET_17") (pintype "input"))
    )
    (net (code "57") (name "Net-(U2-RX0BUF)") (class "Default")
      (node (ref "R46") (pin "2") (pinfunction "2_2") (pintype "passive"))
      (node (ref "U2") (pin "11") (pinfunction "RX0BUF_11") (pintype "output"))
    )
    (net (code "58") (name "Net-(U2-RX1BUF)") (class "Default")
      (node (ref "R47") (pin "1") (pinfunction "1_1") (pintype "passive"))
      (node (ref "U2") (pin "10") (pinfunction "RX1BUF_10") (pintype "output"))
    )
    (net (code "59") (name "Net-(U2-RXCAN)") (class "Default")
      (node (ref "R14") (pin "2") (pinfunction "2_2") (pintype "passive"))
      (node (ref "U2") (pin "2") (pinfunction "RXCAN_2") (pintype "passive"))
    )
    (net (code "60") (name "Net-(U2-SCK)") (class "Default")
      (node (ref "R40") (pin "2") (pinfunction "2_2") (pintype "passive"))
      (node (ref "U2") (pin "13") (pinfunction "SCK_13") (pintype "input"))
    )
    (net (code "61") (name "Net-(U2-SI)") (class "Default")
      (node (ref "R42") (pin "2") (pinfunction "2_2") (pintype "passive"))
      (node (ref "U2") (pin "14") (pinfunction "SI_14") (pintype "input"))
    )
    (net (code "62") (name "Net-(U2-SO)") (class "Default")
      (node (ref "R41") (pin "2") (pinfunction "2_2") (pintype "passive"))
      (node (ref "U2") (pin "15") (pinfunction "SO_15") (pintype "output"))
    )
    (net (code "63") (name "Net-(U2-TX0RTS)") (class "Default")
      (node (ref "R32") (pin "2") (pinfunction "2_2") (pintype "passive"))
      (node (ref "U2") (pin "4") (pinfunction "TX0RTS_4") (pintype "input"))
    )
    (net (code "64") (name "Net-(U2-TX1RTS)") (class "Default")
      (node (ref "R31") (pin "2") (pinfunction "2_2") (pintype "passive"))
      (node (ref "U2") (pin "5") (pinfunction "TX1RTS_5") (pintype "input"))
    )
    (net (code "65") (name "Net-(U2-TX2RTS)") (class "Default")
      (node (ref "R30") (pin "1") (pinfunction "1_1") (pintype "passive"))
      (node (ref "U2") (pin "6") (pinfunction "TX2RTS_6") (pintype "input"))
    )
    (net (code "66") (name "Net-(U2-TXCAN)") (class "Default")
      (node (ref "R15") (pin "2") (pinfunction "2_2") (pintype "passive"))
      (node (ref "U2") (pin "1") (pinfunction "TXCAN_1") (pintype "passive"))
    )
    (net (code "67") (name "Net-(U3-RXD)") (class "Default")
      (node (ref "R11") (pin "1") (pinfunction "1_1") (pintype "passive"))
      (node (ref "U3") (pin "4") (pinfunction "RXD_4") (pintype "output"))
    )
    (net (code "68") (name "Net-(U3-SPLIT)") (class "Default")
      (node (ref "C14") (pin "2") (pinfunction "2_2") (pintype "passive"))
      (node (ref "R16") (pin "2") (pinfunction "2_2") (pintype "passive"))
      (node (ref "R17") (pin "1") (pinfunction "1_1") (pintype "passive"))
      (node (ref "U3") (pin "5") (pinfunction "SPLIT_5") (pintype "passive"))
    )
    (net (code "69") (name "Net-(U3-STB)") (class "Default")
      (node (ref "R13") (pin "1") (pinfunction "1_1") (pintype "passive"))
      (node (ref "U3") (pin "8") (pinfunction "STB_8") (pintype "input"))
    )
    (net (code "70") (name "Net-(U3-TXD)") (class "Default")
      (node (ref "R12") (pin "2") (pinfunction "2_2") (pintype "passive"))
      (node (ref "U3") (pin "1") (pinfunction "TXD_1") (pintype "input"))
    )
    (net (code "71") (name "Net-(U4-RXD)") (class "Default")
      (node (ref "R14") (pin "1") (pinfunction "1_1") (pintype "passive"))
      (node (ref "U4") (pin "4") (pinfunction "RXD_4") (pintype "output"))
    )
    (net (code "72") (name "Net-(U4-SPLIT)") (class "Default")
      (node (ref "C15") (pin "2") (pinfunction "2_2") (pintype "passive"))
      (node (ref "R18") (pin "1") (pinfunction "1_1") (pintype "passive"))
      (node (ref "R19") (pin "2") (pinfunction "2_2") (pintype "passive"))
      (node (ref "U4") (pin "5") (pinfunction "SPLIT_5") (pintype "passive"))
    )
    (net (code "73") (name "Net-(U4-STB)") (class "Default")
      (node (ref "R23") (pin "2") (pinfunction "2_2") (pintype "passive"))
      (node (ref "U4") (pin "8") (pinfunction "STB_8") (pintype "input"))
    )
    (net (code "74") (name "Net-(U4-TXD)") (class "Default")
      (node (ref "R15") (pin "1") (pinfunction "1_1") (pintype "passive"))
      (node (ref "U4") (pin "1") (pinfunction "TXD_1") (pintype "input"))
    )
    (net (code "75") (name "Net-(U5-SHDN)") (class "Default")
      (node (ref "R58") (pin "1") (pinfunction "1_1") (pintype "passive"))
      (node (ref "U5") (pin "3") (pinfunction "SHDN_3") (pintype "open_collector"))
    )
    (net (code "76") (name "Net-(U5-VDD1)") (class "Default")
      (node (ref "C32") (pin "1") (pinfunction "1_1") (pintype "passive"))
      (node (ref "U5") (pin "1") (pinfunction "VDD1_1") (pintype "power_in"))
      (node (ref "VR4") (pin "3") (pinfunction "Vout_3") (pintype "passive"))
    )
    (net (code "77") (name "Net-(U5-Vin)") (class "Default")
      (node (ref "R56") (pin "2") (pinfunction "2_2") (pintype "passive"))
      (node (ref "R57") (pin "2") (pinfunction "2_2") (pintype "passive"))
      (node (ref "U5") (pin "2") (pinfunction "Vin_2") (pintype "input"))
    )
    (net (code "78") (name "Net-(U5-Vout_+)") (class "Default")
      (node (ref "R55") (pin "1") (pinfunction "1_1") (pintype "passive"))
      (node (ref "U5") (pin "7") (pinfunction "Vout_+_7") (pintype "output"))
    )
  )
)
